# oven-controller-v0.net
KiCad netlist of a schematic drawn in EAGLE
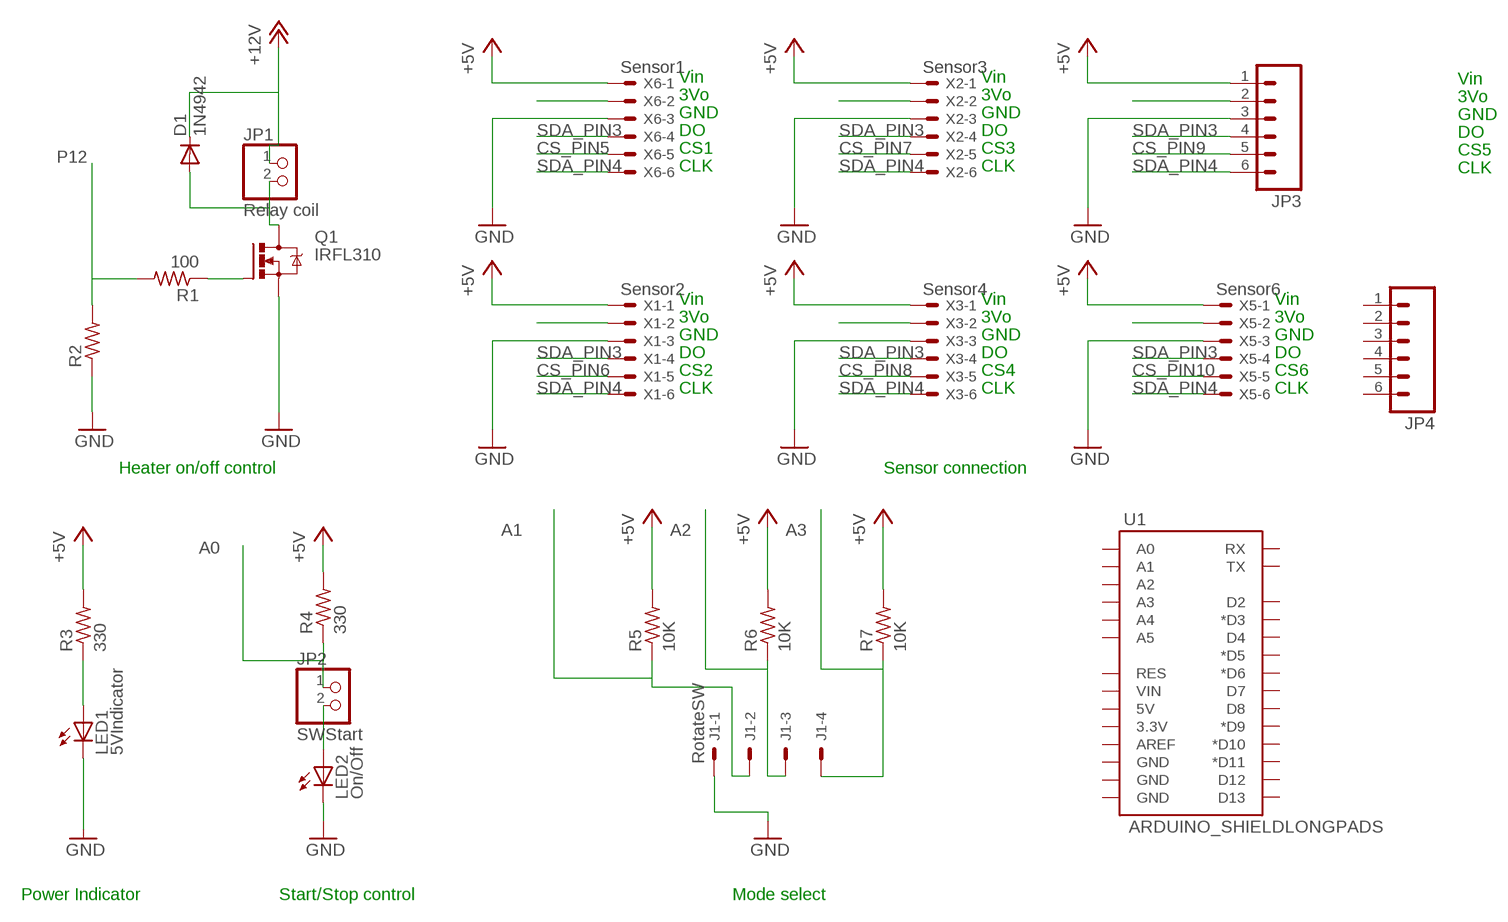
[diagram p0: schematic, sheet 1]

(export (version "E")
  (design (tool "Eeschema 10.0.6"))
  (components
    (comp (ref "D1")
      (value "1N4942")
      (footprint "eagle-import:DO41-10")
      (libsource (lib "eagle-import") (part "1N4942"))
    )
    (comp (ref "J1")
      (value "RotateSW")
      (footprint "eagle-import:6410-04")
      (libsource (lib "eagle-import") (part "22-?-0427-2041"))
    )
    (comp (ref "JP1")
      (value "Relay coil")
      (footprint "eagle-import:1X02")
      (libsource (lib "eagle-import") (part "PINHD-1X2"))
    )
    (comp (ref "JP2")
      (value "SWStart")
      (footprint "eagle-import:1X02")
      (libsource (lib "eagle-import") (part "PINHD-1X2"))
    )
    (comp (ref "JP3")
      (value "M06LOCK_LONGPADS")
      (footprint "eagle-import:1X06_LOCK_LONGPADS")
      (libsource (lib "eagle-import") (part "M06LOCK_LONGPADS"))
    )
    (comp (ref "JP4")
      (value "M06LOCK_LONGPADS")
      (footprint "eagle-import:1X06_LOCK_LONGPADS")
      (libsource (lib "eagle-import") (part "M06LOCK_LONGPADS"))
    )
    (comp (ref "LED1")
      (value "5VIndicator")
      (footprint "eagle-import:LED5MM")
      (libsource (lib "eagle-import") (part "LED5MM"))
    )
    (comp (ref "LED2")
      (value "On/Off")
      (footprint "eagle-import:LED5MM")
      (libsource (lib "eagle-import") (part "LED5MM"))
    )
    (comp (ref "Q1")
      (value "IRFL310")
      (footprint "eagle-import:TO220BV")
      (libsource (lib "eagle-import") (part "IRF520"))
    )
    (comp (ref "R1")
      (value "100")
      (footprint "eagle-import:V234_12")
      (libsource (lib "eagle-import") (part "R-US_V234/12"))
    )
    (comp (ref "R2")
      (value "R-US_V234/12")
      (footprint "eagle-import:V234_12")
      (libsource (lib "eagle-import") (part "R-US_V234/12"))
    )
    (comp (ref "R3")
      (value "330")
      (footprint "eagle-import:0207_10")
      (libsource (lib "eagle-import") (part "R-US_0207/10"))
    )
    (comp (ref "R4")
      (value "330")
      (footprint "eagle-import:0207_10")
      (libsource (lib "eagle-import") (part "R-US_0207/10"))
    )
    (comp (ref "R5")
      (value "10K")
      (footprint "eagle-import:0207_10")
      (libsource (lib "eagle-import") (part "R-US_0207/10"))
    )
    (comp (ref "R6")
      (value "10K")
      (footprint "eagle-import:0207_10")
      (libsource (lib "eagle-import") (part "R-US_0207/10"))
    )
    (comp (ref "R7")
      (value "10K")
      (footprint "eagle-import:0207_10")
      (libsource (lib "eagle-import") (part "R-US_0207/10"))
    )
    (comp (ref "U1")
      (value "ARDUINO_SHIELDLONGPADS")
      (footprint "eagle-import:DUEMILANOVE_SHIELD_LONGPADS")
      (libsource (lib "eagle-import") (part "ARDUINO_SHIELDLONGPADS"))
    )
    (comp (ref "X1")
      (value "Sensor2")
      (footprint "eagle-import:22-23-2061")
      (fields (field (name "MF") "MOLEX") (field (name "MPN") "22-23-2061"))
      (libsource (lib "eagle-import") (part "22-23-2061"))
    )
    (comp (ref "X2")
      (value "Sensor3")
      (footprint "eagle-import:22-23-2061")
      (fields (field (name "MF") "MOLEX") (field (name "MPN") "22-23-2061"))
      (libsource (lib "eagle-import") (part "22-23-2061"))
    )
    (comp (ref "X3")
      (value "Sensor4")
      (footprint "eagle-import:22-23-2061")
      (fields (field (name "MF") "MOLEX") (field (name "MPN") "22-23-2061"))
      (libsource (lib "eagle-import") (part "22-23-2061"))
    )
    (comp (ref "X5")
      (value "Sensor6")
      (footprint "eagle-import:22-23-2061")
      (fields (field (name "MF") "MOLEX") (field (name "MPN") "22-23-2061"))
      (libsource (lib "eagle-import") (part "22-23-2061"))
    )
    (comp (ref "X6")
      (value "Sensor1")
      (footprint "eagle-import:22-23-2061")
      (fields (field (name "MF") "MOLEX") (field (name "MPN") "22-23-2061"))
      (libsource (lib "eagle-import") (part "22-23-2061"))
    )
  )
  (nets
    (net (code "1") (name "+5V") (class "Default")
      (node (ref "JP3") (pin "1") (pinfunction "1_1") (pintype "passive"))
      (node (ref "R3") (pin "2") (pinfunction "2_2") (pintype "passive"))
      (node (ref "R4") (pin "2") (pinfunction "2_2") (pintype "passive"))
      (node (ref "R5") (pin "2") (pinfunction "2_2") (pintype "passive"))
      (node (ref "R6") (pin "2") (pinfunction "2_2") (pintype "passive"))
      (node (ref "R7") (pin "2") (pinfunction "2_2") (pintype "passive"))
      (node (ref "X1") (pin "1") (pinfunction "S_1") (pintype "passive"))
      (node (ref "X2") (pin "1") (pinfunction "S_1") (pintype "passive"))
      (node (ref "X3") (pin "1") (pinfunction "S_1") (pintype "passive"))
      (node (ref "X5") (pin "1") (pinfunction "S_1") (pintype "passive"))
      (node (ref "X6") (pin "1") (pinfunction "S_1") (pintype "passive"))
    )
    (net (code "2") (name "+12V") (class "Default")
      (node (ref "D1") (pin "C") (pinfunction "C_C") (pintype "passive"))
      (node (ref "JP1") (pin "1") (pinfunction "1_1") (pintype "passive"))
    )
    (net (code "3") (name "/A0") (class "Default")
      (node (ref "JP2") (pin "1") (pinfunction "1_1") (pintype "passive"))
      (node (ref "R4") (pin "1") (pinfunction "1_1") (pintype "passive"))
    )
    (net (code "4") (name "/A1") (class "Default")
      (node (ref "J1") (pin "2") (pinfunction "S_2") (pintype "passive"))
      (node (ref "R5") (pin "1") (pinfunction "1_1") (pintype "passive"))
    )
    (net (code "5") (name "/A2") (class "Default")
      (node (ref "J1") (pin "3") (pinfunction "S_3") (pintype "passive"))
      (node (ref "R6") (pin "1") (pinfunction "1_1") (pintype "passive"))
    )
    (net (code "6") (name "/A3") (class "Default")
      (node (ref "J1") (pin "4") (pinfunction "S_4") (pintype "passive"))
      (node (ref "R7") (pin "1") (pinfunction "1_1") (pintype "passive"))
    )
    (net (code "7") (name "/CS_PIN5") (class "Default")
      (node (ref "X6") (pin "5") (pinfunction "S_5") (pintype "passive"))
    )
    (net (code "8") (name "/CS_PIN6") (class "Default")
      (node (ref "X1") (pin "5") (pinfunction "S_5") (pintype "passive"))
    )
    (net (code "9") (name "/CS_PIN7") (class "Default")
      (node (ref "X2") (pin "5") (pinfunction "S_5") (pintype "passive"))
    )
    (net (code "10") (name "/CS_PIN8") (class "Default")
      (node (ref "X3") (pin "5") (pinfunction "S_5") (pintype "passive"))
    )
    (net (code "11") (name "/CS_PIN9") (class "Default")
      (node (ref "JP3") (pin "5") (pinfunction "5_5") (pintype "passive"))
    )
    (net (code "12") (name "/CS_PIN10") (class "Default")
      (node (ref "X5") (pin "5") (pinfunction "S_5") (pintype "passive"))
    )
    (net (code "13") (name "/P12") (class "Default")
      (node (ref "R1") (pin "2") (pinfunction "2_2") (pintype "passive"))
      (node (ref "R2") (pin "2") (pinfunction "2_2") (pintype "passive"))
    )
    (net (code "14") (name "/SDA_PIN3") (class "Default")
      (node (ref "JP3") (pin "4") (pinfunction "4_4") (pintype "passive"))
      (node (ref "X1") (pin "4") (pinfunction "S_4") (pintype "passive"))
      (node (ref "X2") (pin "4") (pinfunction "S_4") (pintype "passive"))
      (node (ref "X3") (pin "4") (pinfunction "S_4") (pintype "passive"))
      (node (ref "X5") (pin "4") (pinfunction "S_4") (pintype "passive"))
      (node (ref "X6") (pin "4") (pinfunction "S_4") (pintype "passive"))
    )
    (net (code "15") (name "/SDA_PIN4") (class "Default")
      (node (ref "JP3") (pin "6") (pinfunction "6_6") (pintype "passive"))
      (node (ref "X1") (pin "6") (pinfunction "S_6") (pintype "passive"))
      (node (ref "X2") (pin "6") (pinfunction "S_6") (pintype "passive"))
      (node (ref "X3") (pin "6") (pinfunction "S_6") (pintype "passive"))
      (node (ref "X5") (pin "6") (pinfunction "S_6") (pintype "passive"))
      (node (ref "X6") (pin "6") (pinfunction "S_6") (pintype "passive"))
    )
    (net (code "16") (name "GND") (class "Default")
      (node (ref "J1") (pin "1") (pinfunction "S_1") (pintype "passive"))
      (node (ref "JP3") (pin "3") (pinfunction "3_3") (pintype "passive"))
      (node (ref "LED2") (pin "K") (pinfunction "C_K") (pintype "passive"))
      (node (ref "Q1") (pin "S") (pinfunction "S_S") (pintype "passive"))
      (node (ref "R2") (pin "1") (pinfunction "1_1") (pintype "passive"))
      (node (ref "X1") (pin "3") (pinfunction "S_3") (pintype "passive"))
      (node (ref "X2") (pin "3") (pinfunction "S_3") (pintype "passive"))
      (node (ref "X3") (pin "3") (pinfunction "S_3") (pintype "passive"))
      (node (ref "X5") (pin "3") (pinfunction "S_3") (pintype "passive"))
      (node (ref "X6") (pin "3") (pinfunction "S_3") (pintype "passive"))
    )
    (net (code "17") (name "Net-(D1-PadA)") (class "Default")
      (node (ref "D1") (pin "A") (pinfunction "A_A") (pintype "passive"))
      (node (ref "JP1") (pin "2") (pinfunction "2_2") (pintype "passive"))
      (node (ref "Q1") (pin "D") (pinfunction "D_D") (pintype "passive"))
    )
    (net (code "18") (name "Net-(JP2-Pad2)") (class "Default")
      (node (ref "JP2") (pin "2") (pinfunction "2_2") (pintype "passive"))
      (node (ref "LED2") (pin "A") (pinfunction "A_A") (pintype "passive"))
    )
    (net (code "19") (name "Net-(LED1-PadA)") (class "Default")
      (node (ref "LED1") (pin "A") (pinfunction "A_A") (pintype "passive"))
      (node (ref "R3") (pin "1") (pinfunction "1_1") (pintype "passive"))
    )
    (net (code "20") (name "Net-(Q1-PadG)") (class "Default")
      (node (ref "Q1") (pin "G") (pinfunction "G_G") (pintype "passive"))
      (node (ref "R1") (pin "1") (pinfunction "1_1") (pintype "passive"))
    )
    (net (code "21") (name "unconnected-(JP3-Pad2)") (class "Default")
      (node (ref "JP3") (pin "2") (pinfunction "2_2") (pintype "passive"))
    )
    (net (code "22") (name "unconnected-(JP4-Pad1)") (class "Default")
      (node (ref "JP4") (pin "1") (pinfunction "1_1") (pintype "passive"))
    )
    (net (code "23") (name "unconnected-(JP4-Pad2)") (class "Default")
      (node (ref "JP4") (pin "2") (pinfunction "2_2") (pintype "passive"))
    )
    (net (code "24") (name "unconnected-(JP4-Pad3)") (class "Default")
      (node (ref "JP4") (pin "3") (pinfunction "3_3") (pintype "passive"))
    )
    (net (code "25") (name "unconnected-(JP4-Pad4)") (class "Default")
      (node (ref "JP4") (pin "4") (pinfunction "4_4") (pintype "passive"))
    )
    (net (code "26") (name "unconnected-(JP4-Pad5)") (class "Default")
      (node (ref "JP4") (pin "5") (pinfunction "5_5") (pintype "passive"))
    )
    (net (code "27") (name "unconnected-(JP4-Pad6)") (class "Default")
      (node (ref "JP4") (pin "6") (pinfunction "6_6") (pintype "passive"))
    )
    (net (code "28") (name "unconnected-(LED1-C-PadK)") (class "Default")
      (node (ref "LED1") (pin "K") (pinfunction "C_K") (pintype "passive"))
    )
    (net (code "29") (name "unconnected-(U1-*D3-PadD3)") (class "Default")
      (node (ref "U1") (pin "D3") (pinfunction "*D3_D3") (pintype "bidirectional"))
    )
    (net (code "30") (name "unconnected-(U1-*D5-PadD5)") (class "Default")
      (node (ref "U1") (pin "D5") (pinfunction "*D5_D5") (pintype "bidirectional"))
    )
    (net (code "31") (name "unconnected-(U1-*D6-PadD6)") (class "Default")
      (node (ref "U1") (pin "D6") (pinfunction "*D6_D6") (pintype "bidirectional"))
    )
    (net (code "32") (name "unconnected-(U1-*D9-PadD9)") (class "Default")
      (node (ref "U1") (pin "D9") (pinfunction "*D9_D9") (pintype "bidirectional"))
    )
    (net (code "33") (name "unconnected-(U1-*D10-PadD10)") (class "Default")
      (node (ref "U1") (pin "D10") (pinfunction "*D10_D10") (pintype "bidirectional"))
    )
    (net (code "34") (name "unconnected-(U1-*D11-PadD11)") (class "Default")
      (node (ref "U1") (pin "D11") (pinfunction "*D11_D11") (pintype "bidirectional"))
    )
    (net (code "35") (name "unconnected-(U1-GND-PadGND@0)") (class "Default")
      (node (ref "U1") (pin "GND@0") (pinfunction "GND_GND@0") (pintype "bidirectional"))
    )
    (net (code "36") (name "unconnected-(U1-GND-PadGND@1)") (class "Default")
      (node (ref "U1") (pin "GND@1") (pinfunction "GND_GND@1") (pintype "bidirectional"))
    )
    (net (code "37") (name "unconnected-(U1-GND-PadGND@2)") (class "Default")
      (node (ref "U1") (pin "GND@2") (pinfunction "GND_GND@2") (pintype "bidirectional"))
    )
    (net (code "38") (name "unconnected-(U1-Pad3.3V)") (class "Default")
      (node (ref "U1") (pin "3.3V") (pinfunction "3.3V_3.3V") (pintype "bidirectional"))
    )
    (net (code "39") (name "unconnected-(U1-Pad5V)") (class "Default")
      (node (ref "U1") (pin "5V") (pinfunction "5V_5V") (pintype "bidirectional"))
    )
    (net (code "40") (name "unconnected-(U1-PadA0)") (class "Default")
      (node (ref "U1") (pin "A0") (pinfunction "A0_A0") (pintype "bidirectional"))
    )
    (net (code "41") (name "unconnected-(U1-PadA1)") (class "Default")
      (node (ref "U1") (pin "A1") (pinfunction "A1_A1") (pintype "bidirectional"))
    )
    (net (code "42") (name "unconnected-(U1-PadA2)") (class "Default")
      (node (ref "U1") (pin "A2") (pinfunction "A2_A2") (pintype "bidirectional"))
    )
    (net (code "43") (name "unconnected-(U1-PadA3)") (class "Default")
      (node (ref "U1") (pin "A3") (pinfunction "A3_A3") (pintype "bidirectional"))
    )
    (net (code "44") (name "unconnected-(U1-PadA4)") (class "Default")
      (node (ref "U1") (pin "A4") (pinfunction "A4_A4") (pintype "bidirectional"))
    )
    (net (code "45") (name "unconnected-(U1-PadA5)") (class "Default")
      (node (ref "U1") (pin "A5") (pinfunction "A5_A5") (pintype "bidirectional"))
    )
    (net (code "46") (name "unconnected-(U1-PadAREF)") (class "Default")
      (node (ref "U1") (pin "AREF") (pinfunction "AREF_AREF") (pintype "bidirectional"))
    )
    (net (code "47") (name "unconnected-(U1-PadD2)") (class "Default")
      (node (ref "U1") (pin "D2") (pinfunction "D2_D2") (pintype "bidirectional"))
    )
    (net (code "48") (name "unconnected-(U1-PadD4)") (class "Default")
      (node (ref "U1") (pin "D4") (pinfunction "D4_D4") (pintype "bidirectional"))
    )
    (net (code "49") (name "unconnected-(U1-PadD7)") (class "Default")
      (node (ref "U1") (pin "D7") (pinfunction "D7_D7") (pintype "bidirectional"))
    )
    (net (code "50") (name "unconnected-(U1-PadD8)") (class "Default")
      (node (ref "U1") (pin "D8") (pinfunction "D8_D8") (pintype "bidirectional"))
    )
    (net (code "51") (name "unconnected-(U1-PadD12)") (class "Default")
      (node (ref "U1") (pin "D12") (pinfunction "D12_D12") (pintype "bidirectional"))
    )
    (net (code "52") (name "unconnected-(U1-PadD13)") (class "Default")
      (node (ref "U1") (pin "D13") (pinfunction "D13_D13") (pintype "bidirectional"))
    )
    (net (code "53") (name "unconnected-(U1-PadRES)") (class "Default")
      (node (ref "U1") (pin "RES") (pinfunction "RES_RES") (pintype "bidirectional"))
    )
    (net (code "54") (name "unconnected-(U1-PadRX)") (class "Default")
      (node (ref "U1") (pin "RX") (pinfunction "RX_RX") (pintype "bidirectional"))
    )
    (net (code "55") (name "unconnected-(U1-PadTX)") (class "Default")
      (node (ref "U1") (pin "TX") (pinfunction "TX_TX") (pintype "bidirectional"))
    )
    (net (code "56") (name "unconnected-(U1-PadVIN)") (class "Default")
      (node (ref "U1") (pin "VIN") (pinfunction "VIN_VIN") (pintype "bidirectional"))
    )
    (net (code "57") (name "unconnected-(X1B-S-Pad2)") (class "Default")
      (node (ref "X1") (pin "2") (pinfunction "S_2") (pintype "passive"))
    )
    (net (code "58") (name "unconnected-(X2B-S-Pad2)") (class "Default")
      (node (ref "X2") (pin "2") (pinfunction "S_2") (pintype "passive"))
    )
    (net (code "59") (name "unconnected-(X3B-S-Pad2)") (class "Default")
      (node (ref "X3") (pin "2") (pinfunction "S_2") (pintype "passive"))
    )
    (net (code "60") (name "unconnected-(X5B-S-Pad2)") (class "Default")
      (node (ref "X5") (pin "2") (pinfunction "S_2") (pintype "passive"))
    )
    (net (code "61") (name "unconnected-(X6B-S-Pad2)") (class "Default")
      (node (ref "X6") (pin "2") (pinfunction "S_2") (pintype "passive"))
    )
  )
)
